# Master.net
KiCad netlist of a schematic drawn in Altium Designer
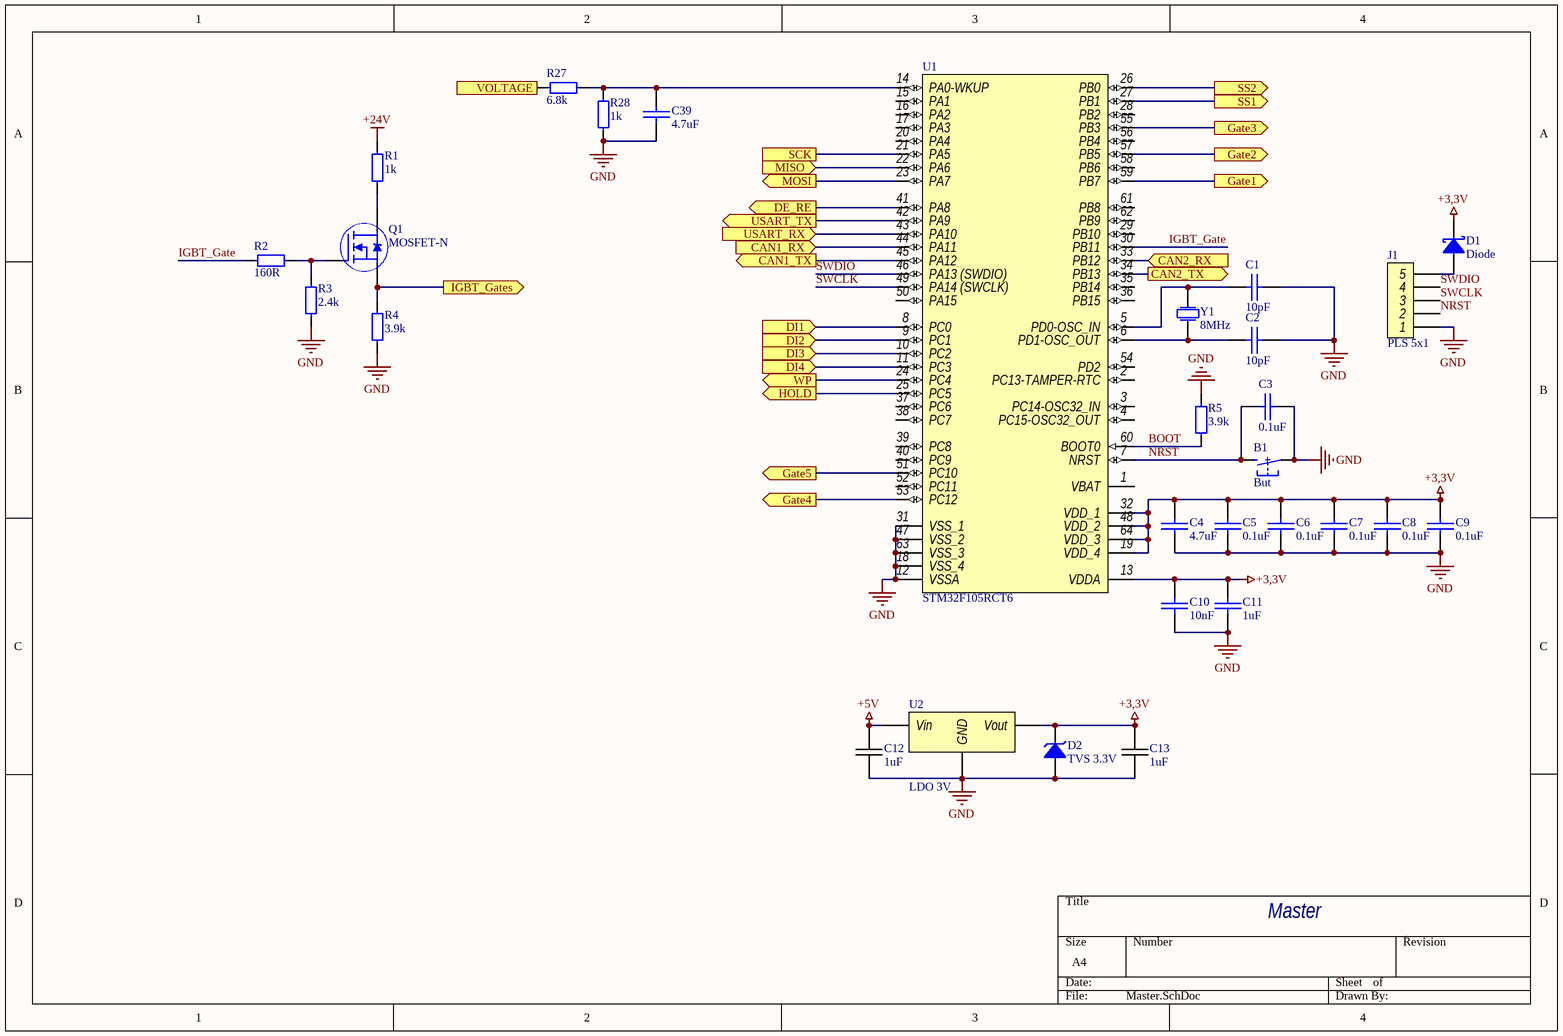
[diagram p0: Master.SchDoc]

(export (version "E")
  (design (tool "Eeschema 10.0.6"))
  (components
    (comp (ref "B1")
      (value "But")
      (footprint "BUTTON 6x3.5")
      (description "Button 2 Conn SMD")
      (fields
        (field (name "PART NUMBER") "L-KLS7-TS3608-5.0-180")
        (field (name "MANUFACTURER") "KLS electronic co ltd")
      )
      (libsource (lib "БУС") (part "Button 2 Conn"))
    )
    (comp (ref "C1")
      (value "10pF")
      (footprint "0603 Capicator")
      (description "10pF NP0 50V 5% 0603")
      (fields
        (field (name "MANUFACTURER") "Murata Manufacturing")
        (field (name "PART NUMBER") "GRM1885C1H100JA01D")
      )
      (libsource (lib "БУС") (part "Cap 10pF (0603)"))
    )
    (comp (ref "C2")
      (value "10pF")
      (footprint "0603 Capicator")
      (description "10pF NP0 50V 5% 0603")
      (fields
        (field (name "MANUFACTURER") "Murata Manufacturing")
        (field (name "PART NUMBER") "GRM1885C1H100JA01D")
      )
      (libsource (lib "БУС") (part "Cap 10pF (0603)"))
    )
    (comp (ref "C3")
      (value "0.1uF")
      (footprint "0603 Capicator")
      (description "0.1uF X7R 16V 10% 0603")
      (fields
        (field (name "MANUFACTURER") "Murata Manufacturing")
        (field (name "PART NUMBER") "GRM188R71C104KA01D")
      )
      (libsource (lib "БУС") (part "Cap 0.1uF (0603)"))
    )
    (comp (ref "C4")
      (value "4.7uF")
      (footprint "0603 Capicator")
      (description "4.7uF X5R 25V 10% 0603")
      (fields
        (field (name "MANUFACTURER") "Murata Manufacturing")
        (field (name "PART NUMBER") "GRM188R61E475KE11D")
      )
      (libsource (lib "БУС") (part "Cap 4.7uF (0603)"))
    )
    (comp (ref "C5")
      (value "0.1uF")
      (footprint "0603 Capicator")
      (description "0.1uF X7R 16V 10% 0603")
      (fields
        (field (name "MANUFACTURER") "Murata Manufacturing")
        (field (name "PART NUMBER") "GRM188R71C104KA01D")
      )
      (libsource (lib "БУС") (part "Cap 0.1uF (0603)"))
    )
    (comp (ref "C6")
      (value "0.1uF")
      (footprint "0603 Capicator")
      (description "0.1uF X7R 16V 10% 0603")
      (fields
        (field (name "MANUFACTURER") "Murata Manufacturing")
        (field (name "PART NUMBER") "GRM188R71C104KA01D")
      )
      (libsource (lib "БУС") (part "Cap 0.1uF (0603)"))
    )
    (comp (ref "C7")
      (value "0.1uF")
      (footprint "0603 Capicator")
      (description "0.1uF X7R 16V 10% 0603")
      (fields
        (field (name "MANUFACTURER") "Murata Manufacturing")
        (field (name "PART NUMBER") "GRM188R71C104KA01D")
      )
      (libsource (lib "БУС") (part "Cap 0.1uF (0603)"))
    )
    (comp (ref "C8")
      (value "0.1uF")
      (footprint "0603 Capicator")
      (description "0.1uF X7R 16V 10% 0603")
      (fields
        (field (name "MANUFACTURER") "Murata Manufacturing")
        (field (name "PART NUMBER") "GRM188R71C104KA01D")
      )
      (libsource (lib "БУС") (part "Cap 0.1uF (0603)"))
    )
    (comp (ref "C9")
      (value "0.1uF")
      (footprint "0603 Capicator")
      (description "0.1uF X7R 16V 10% 0603")
      (fields
        (field (name "MANUFACTURER") "Murata Manufacturing")
        (field (name "PART NUMBER") "GRM188R71C104KA01D")
      )
      (libsource (lib "БУС") (part "Cap 0.1uF (0603)"))
    )
    (comp (ref "C10")
      (value "10nF")
      (footprint "0603 Capicator")
      (description "10nF X7R  100V 10% 0603")
      (fields
        (field (name "MANUFACTURER") "Murata Manufacturing")
        (field (name "PART NUMBER") "GRM188R72A103KA01D")
      )
      (libsource (lib "БУС") (part "Cap 10nF (0603)"))
    )
    (comp (ref "C11")
      (value "1uF")
      (footprint "0603 Capicator")
      (description "1uF X5R 25V 10% 0603")
      (fields
        (field (name "MANUFACTURER") "Murata Manufacturing")
        (field (name "PART NUMBER") "GRM188R61E105KAADD")
      )
      (libsource (lib "БУС") (part "Cap 1uF (0603)"))
    )
    (comp (ref "C12")
      (value "1uF")
      (footprint "0603 Capicator")
      (description "1uF X5R 25V 10% 0603")
      (fields
        (field (name "MANUFACTURER") "Murata Manufacturing")
        (field (name "PART NUMBER") "GRM188R61E105KAADD")
      )
      (libsource (lib "БУС") (part "Cap 1uF (0603)"))
    )
    (comp (ref "C13")
      (value "1uF")
      (footprint "0603 Capicator")
      (description "1uF X5R 25V 10% 0603")
      (fields
        (field (name "MANUFACTURER") "Murata Manufacturing")
        (field (name "PART NUMBER") "GRM188R61E105KAADD")
      )
      (libsource (lib "БУС") (part "Cap 1uF (0603)"))
    )
    (comp (ref "C39")
      (value "4.7uF")
      (footprint "0603 Capicator")
      (description "4.7uF X5R 25V 10% 0603")
      (fields
        (field (name "MANUFACTURER") "Murata Manufacturing")
        (field (name "PART NUMBER") "GRM188R61E475KE11D")
      )
      (libsource (lib "БУНЭ") (part "Cap 4.7uF (0603)"))
    )
    (comp (ref "D1")
      (value "Diode")
      (footprint "sod-123")
      (description "0.5 A, Low Forward Voltage less than 385 mV, 400 mW Power Dissipation Package")
      (fields (field (name "PART NUMBER") "MBR0520L") (field (name "MANUFACTURER") "ON Semiconductor"))
      (libsource (lib "БУС") (part "Diode Schottky (SOD-123)"))
    )
    (comp (ref "D2")
      (value "TVS 3.3V")
      (footprint "DO-216AA")
      (description "High peak pulse power: 200 W (10/1000 μs)")
      (fields (field (name "PART NUMBER") "SM2T3V3A") (field (name "MANUFACTURER") "STMicroelectronics"))
      (libsource (lib "БУС") (part "TVS Diode 3.3V [SM2T]"))
    )
    (comp (ref "J1")
      (value "PLS 5x1")
      (footprint "PLS 5x1")
      (description "Header, 5-Pin")
      (libsource (lib "БУС") (part "Conn 5 (PLS)"))
    )
    (comp (ref "Q1")
      (value "MOSFET-N")
      (footprint "SOT-23")
      (description "VDS 30V,  VGS Max ± 20V, RDS 27-40mΩ,")
      (fields
        (field (name "PART NUMBER") "IRLML0030TRPBF")
        (field (name "MANUFACTURER") "Infineon Technologies")
      )
      (libsource (lib "БУНЭ") (part "MOSFET-N [IRLML]"))
    )
    (comp (ref "R1")
      (value "1k")
      (footprint "0603 Resistor")
      (description "0.1W 0603 1k, 1%")
      (fields (field (name "PART NUMBER") "RC0603FR-071KL") (field (name "MANUFACTURER") "Taiwan"))
      (libsource (lib "БУНЭ") (part "Res 1k (0603)"))
    )
    (comp (ref "R2")
      (value "160R")
      (footprint "0603 Resistor")
      (description "0.1W 0603 160R, 1%")
      (fields (field (name "PART NUMBER") "RC0603FR-07160RL") (field (name "MANUFACTURER") "Taiwan"))
      (libsource (lib "БУС") (part "Res 160R (0603)"))
    )
    (comp (ref "R3")
      (value "2.4k")
      (footprint "0603 Resistor")
      (description "0.1W 0603 2.4k, 1%")
      (fields (field (name "PART NUMBER") "RC0603FR-072K4L") (field (name "MANUFACTURER") "Taiwan"))
      (libsource (lib "БУС") (part "Res 2.4k (0603)"))
    )
    (comp (ref "R4")
      (value "3.9k")
      (footprint "0603 Resistor")
      (description "0.1W 0603 3.9k, 1%")
      (fields (field (name "PART NUMBER") "RC0603FR-073K9L") (field (name "MANUFACTURER") "Taiwan"))
      (libsource (lib "БУНЭ") (part "Res 3.9k (0603)"))
    )
    (comp (ref "R5")
      (value "3.9k")
      (footprint "0603 Resistor")
      (description "0.1W 0603 3.9k, 1%")
      (fields (field (name "PART NUMBER") "RC0603FR-073K9L") (field (name "MANUFACTURER") "Taiwan"))
      (libsource (lib "БУС") (part "Res 3.9k (0603)"))
    )
    (comp (ref "R27")
      (value "6.8k")
      (footprint "0603 Resistor")
      (description "0.1W 0603 6.8k, 1%")
      (fields (field (name "PART NUMBER") "RC0603FR-076K8L") (field (name "MANUFACTURER") "Taiwan"))
      (libsource (lib "БУНЭ") (part "Res 6.8k (0603)"))
    )
    (comp (ref "R28")
      (value "1k")
      (footprint "0603 Resistor")
      (description "0.1W 0603 1k, 1%")
      (fields (field (name "PART NUMBER") "RC0603FR-071KL") (field (name "MANUFACTURER") "Taiwan"))
      (libsource (lib "БУНЭ") (part "Res 1k (0603)"))
    )
    (comp (ref "U1")
      (value "STM32F105RCT6")
      (footprint "LQFP64")
      (description "MCU ARM 256KB FLASH MEM 64-LQFP")
      (fields (field (name "MANUFACTURER") "STMicroelectronics"))
      (libsource (lib "БУС") (part "STM32F105RCT6"))
    )
    (comp (ref "U2")
      (value "LDO 3V")
      (footprint "SOT-23")
      (description "MCP1702 Low Dropout Voltage Regulator. The input operating range is specifiedfrom 2.7V to 13.2V")
      (fields (field (name "PART NUMBER") "MCP1702T-3002E/CB") (field (name "MANUFACTURER") "Microchip"))
      (libsource (lib "БУС") (part "LDO 3,3V [MCP]"))
    )
    (comp (ref "Y1")
      (value "8MHz")
      (footprint "NX5032GA")
      (description "Crystal NX5032GA")
      (fields
        (field (name "MANUFACTURER") "Nihon Dempa Kogio (NDK)")
        (field (name "PART NUMBER") "NX5032GA-8MHz")
      )
      (libsource (lib "БУС") (part "Crystal 8MHz"))
    )
  )
  (nets
    (net (code "1") (name "+3,3V") (class "Default")
      (node (ref "C10") (pin "2") (pinfunction "2_2") (pintype "passive"))
      (node (ref "C11") (pin "2") (pinfunction "2_2") (pintype "passive"))
      (node (ref "C13") (pin "2") (pinfunction "2_2") (pintype "passive"))
      (node (ref "C4") (pin "2") (pinfunction "2_2") (pintype "passive"))
      (node (ref "C5") (pin "2") (pinfunction "2_2") (pintype "passive"))
      (node (ref "C6") (pin "2") (pinfunction "2_2") (pintype "passive"))
      (node (ref "C7") (pin "2") (pinfunction "2_2") (pintype "passive"))
      (node (ref "C8") (pin "2") (pinfunction "2_2") (pintype "passive"))
      (node (ref "C9") (pin "2") (pinfunction "2_2") (pintype "passive"))
      (node (ref "D1") (pin "2") (pinfunction "2_2") (pintype "passive"))
      (node (ref "D2") (pin "2") (pinfunction "2_2") (pintype "passive"))
      (node (ref "U1") (pin "13") (pinfunction "VDDA_13") (pintype "power_in"))
      (node (ref "U1") (pin "19") (pinfunction "VDD_4_19") (pintype "power_in"))
      (node (ref "U1") (pin "32") (pinfunction "VDD_1_32") (pintype "power_in"))
      (node (ref "U1") (pin "48") (pinfunction "VDD_2_48") (pintype "power_in"))
      (node (ref "U1") (pin "64") (pinfunction "VDD_3_64") (pintype "power_in"))
      (node (ref "U2") (pin "2") (pinfunction "Vout_2") (pintype "power_in"))
    )
    (net (code "2") (name "+5V") (class "Default")
      (node (ref "C12") (pin "2") (pinfunction "2_2") (pintype "passive"))
      (node (ref "U2") (pin "3") (pinfunction "Vin_3") (pintype "power_in"))
    )
    (net (code "3") (name "+24V") (class "Default")
      (node (ref "R1") (pin "2") (pinfunction "2_2") (pintype "passive"))
    )
    (net (code "4") (name "/BOOT") (class "Default")
      (node (ref "R5") (pin "1") (pinfunction "1_1") (pintype "passive"))
      (node (ref "U1") (pin "60") (pinfunction "BOOT0_60") (pintype "input"))
    )
    (net (code "5") (name "/CAN1_RX") (class "Default")
      (node (ref "U1") (pin "44") (pinfunction "PA11_44") (pintype "bidirectional"))
    )
    (net (code "6") (name "/CAN1_TX") (class "Default")
      (node (ref "U1") (pin "45") (pinfunction "PA12_45") (pintype "bidirectional"))
    )
    (net (code "7") (name "/CAN2_RX") (class "Default")
      (node (ref "U1") (pin "33") (pinfunction "PB12_33") (pintype "bidirectional"))
    )
    (net (code "8") (name "/CAN2_TX") (class "Default")
      (node (ref "U1") (pin "34") (pinfunction "PB13_34") (pintype "bidirectional"))
    )
    (net (code "9") (name "/DE_RE") (class "Default")
      (node (ref "U1") (pin "41") (pinfunction "PA8_41") (pintype "bidirectional"))
    )
    (net (code "10") (name "/DI1") (class "Default")
      (node (ref "U1") (pin "8") (pinfunction "PC0_8") (pintype "bidirectional"))
    )
    (net (code "11") (name "/DI2") (class "Default")
      (node (ref "U1") (pin "9") (pinfunction "PC1_9") (pintype "bidirectional"))
    )
    (net (code "12") (name "/DI3") (class "Default")
      (node (ref "U1") (pin "10") (pinfunction "PC2_10") (pintype "bidirectional"))
    )
    (net (code "13") (name "/DI4") (class "Default")
      (node (ref "U1") (pin "11") (pinfunction "PC3_11") (pintype "bidirectional"))
    )
    (net (code "14") (name "/Gate1") (class "Default")
      (node (ref "U1") (pin "59") (pinfunction "PB7_59") (pintype "bidirectional"))
    )
    (net (code "15") (name "/Gate2") (class "Default")
      (node (ref "U1") (pin "57") (pinfunction "PB5_57") (pintype "bidirectional"))
    )
    (net (code "16") (name "/Gate3") (class "Default")
      (node (ref "U1") (pin "55") (pinfunction "PB3_55") (pintype "bidirectional"))
    )
    (net (code "17") (name "/Gate4") (class "Default")
      (node (ref "U1") (pin "53") (pinfunction "PC12_53") (pintype "bidirectional"))
    )
    (net (code "18") (name "/Gate5") (class "Default")
      (node (ref "U1") (pin "51") (pinfunction "PC10_51") (pintype "bidirectional"))
    )
    (net (code "19") (name "/HOLD") (class "Default")
      (node (ref "U1") (pin "25") (pinfunction "PC5_25") (pintype "bidirectional"))
    )
    (net (code "20") (name "/IGBT_Gate") (class "Default")
      (node (ref "R2") (pin "1") (pinfunction "1_1") (pintype "passive"))
      (node (ref "U1") (pin "30") (pinfunction "PB11_30") (pintype "bidirectional"))
    )
    (net (code "21") (name "/IGBT_Gates") (class "Default")
      (node (ref "Q1") (pin "2") (pinfunction "Source_2") (pintype "passive"))
      (node (ref "R4") (pin "2") (pinfunction "2_2") (pintype "passive"))
    )
    (net (code "22") (name "/MISO") (class "Default")
      (node (ref "U1") (pin "22") (pinfunction "PA6_22") (pintype "bidirectional"))
    )
    (net (code "23") (name "/MOSI") (class "Default")
      (node (ref "U1") (pin "23") (pinfunction "PA7_23") (pintype "bidirectional"))
    )
    (net (code "24") (name "/NRST") (class "Default")
      (node (ref "B1") (pin "2") (pinfunction "2_2") (pintype "passive"))
      (node (ref "C3") (pin "1") (pinfunction "1_1") (pintype "passive"))
      (node (ref "J1") (pin "2") (pinfunction "2_2") (pintype "passive"))
      (node (ref "U1") (pin "7") (pinfunction "NRST_7") (pintype "bidirectional"))
    )
    (net (code "25") (name "/SCK") (class "Default")
      (node (ref "U1") (pin "21") (pinfunction "PA5_21") (pintype "bidirectional"))
    )
    (net (code "26") (name "/SS1") (class "Default")
      (node (ref "U1") (pin "27") (pinfunction "PB1_27") (pintype "bidirectional"))
    )
    (net (code "27") (name "/SS2") (class "Default")
      (node (ref "U1") (pin "26") (pinfunction "PB0_26") (pintype "bidirectional"))
    )
    (net (code "28") (name "/SWCLK") (class "Default")
      (node (ref "J1") (pin "3") (pinfunction "3_3") (pintype "passive"))
      (node (ref "U1") (pin "49") (pinfunction "PA14_(SWCLK)_49") (pintype "bidirectional"))
    )
    (net (code "29") (name "/SWDIO") (class "Default")
      (node (ref "J1") (pin "4") (pinfunction "4_4") (pintype "passive"))
      (node (ref "U1") (pin "46") (pinfunction "PA13_(SWDIO)_46") (pintype "bidirectional"))
    )
    (net (code "30") (name "/USART_RX") (class "Default")
      (node (ref "U1") (pin "43") (pinfunction "PA10_43") (pintype "bidirectional"))
    )
    (net (code "31") (name "/USART_TX") (class "Default")
      (node (ref "U1") (pin "42") (pinfunction "PA9_42") (pintype "bidirectional"))
    )
    (net (code "32") (name "/VOLTAGE") (class "Default")
      (node (ref "R27") (pin "2") (pinfunction "2_2") (pintype "passive"))
    )
    (net (code "33") (name "/WP") (class "Default")
      (node (ref "U1") (pin "24") (pinfunction "PC4_24") (pintype "bidirectional"))
    )
    (net (code "34") (name "GND") (class "Default")
      (node (ref "B1") (pin "1") (pinfunction "1_1") (pintype "passive"))
      (node (ref "C1") (pin "2") (pinfunction "2_2") (pintype "passive"))
      (node (ref "C10") (pin "1") (pinfunction "1_1") (pintype "passive"))
      (node (ref "C11") (pin "1") (pinfunction "1_1") (pintype "passive"))
      (node (ref "C12") (pin "1") (pinfunction "1_1") (pintype "passive"))
      (node (ref "C13") (pin "1") (pinfunction "1_1") (pintype "passive"))
      (node (ref "C2") (pin "2") (pinfunction "2_2") (pintype "passive"))
      (node (ref "C3") (pin "2") (pinfunction "2_2") (pintype "passive"))
      (node (ref "C39") (pin "1") (pinfunction "1_1") (pintype "passive"))
      (node (ref "C4") (pin "1") (pinfunction "1_1") (pintype "passive"))
      (node (ref "C5") (pin "1") (pinfunction "1_1") (pintype "passive"))
      (node (ref "C6") (pin "1") (pinfunction "1_1") (pintype "passive"))
      (node (ref "C7") (pin "1") (pinfunction "1_1") (pintype "passive"))
      (node (ref "C8") (pin "1") (pinfunction "1_1") (pintype "passive"))
      (node (ref "C9") (pin "1") (pinfunction "1_1") (pintype "passive"))
      (node (ref "D2") (pin "1") (pinfunction "1_1") (pintype "passive"))
      (node (ref "J1") (pin "1") (pinfunction "1_1") (pintype "passive"))
      (node (ref "R28") (pin "1") (pinfunction "1_1") (pintype "passive"))
      (node (ref "R3") (pin "1") (pinfunction "1_1") (pintype "passive"))
      (node (ref "R4") (pin "1") (pinfunction "1_1") (pintype "passive"))
      (node (ref "R5") (pin "2") (pinfunction "2_2") (pintype "passive"))
      (node (ref "U1") (pin "12") (pinfunction "VSSA_12") (pintype "power_in"))
      (node (ref "U1") (pin "18") (pinfunction "VSS_4_18") (pintype "power_in"))
      (node (ref "U1") (pin "31") (pinfunction "VSS_1_31") (pintype "power_in"))
      (node (ref "U1") (pin "47") (pinfunction "VSS_2_47") (pintype "power_in"))
      (node (ref "U1") (pin "63") (pinfunction "VSS_3_63") (pintype "power_in"))
      (node (ref "U2") (pin "1") (pinfunction "GND_1") (pintype "power_in"))
    )
    (net (code "35") (name "Net-(D1-Pad1)") (class "Default")
      (node (ref "D1") (pin "1") (pinfunction "1_1") (pintype "passive"))
      (node (ref "J1") (pin "5") (pinfunction "5_5") (pintype "passive"))
    )
    (net (code "36") (name "Net-(Q1-Drain)") (class "Default")
      (node (ref "Q1") (pin "3") (pinfunction "Drain_3") (pintype "passive"))
      (node (ref "R1") (pin "1") (pinfunction "1_1") (pintype "passive"))
    )
    (net (code "37") (name "Net-(Q1-Gate)") (class "Default")
      (node (ref "Q1") (pin "1") (pinfunction "Gate_1") (pintype "passive"))
      (node (ref "R2") (pin "2") (pinfunction "2_2") (pintype "passive"))
      (node (ref "R3") (pin "2") (pinfunction "2_2") (pintype "passive"))
    )
    (net (code "38") (name "Net-(U1-PA0-WKUP)") (class "Default")
      (node (ref "C39") (pin "2") (pinfunction "2_2") (pintype "passive"))
      (node (ref "R27") (pin "1") (pinfunction "1_1") (pintype "passive"))
      (node (ref "R28") (pin "2") (pinfunction "2_2") (pintype "passive"))
      (node (ref "U1") (pin "14") (pinfunction "PA0-WKUP_14") (pintype "bidirectional"))
    )
    (net (code "39") (name "Net-(U1-PD0-OSC_IN)") (class "Default")
      (node (ref "C1") (pin "1") (pinfunction "1_1") (pintype "passive"))
      (node (ref "U1") (pin "5") (pinfunction "PD0-OSC_IN_5") (pintype "bidirectional"))
      (node (ref "Y1") (pin "2") (pinfunction "2_2") (pintype "passive"))
    )
    (net (code "40") (name "Net-(U1-PD1-OSC_OUT)") (class "Default")
      (node (ref "C2") (pin "1") (pinfunction "1_1") (pintype "passive"))
      (node (ref "U1") (pin "6") (pinfunction "PD1-OSC_OUT_6") (pintype "bidirectional"))
      (node (ref "Y1") (pin "1") (pinfunction "1_1") (pintype "passive"))
    )
    (net (code "41") (name "unconnected-(U1-PA1-Pad15)") (class "Default")
      (node (ref "U1") (pin "15") (pinfunction "PA1_15") (pintype "bidirectional"))
    )
    (net (code "42") (name "unconnected-(U1-PA2-Pad16)") (class "Default")
      (node (ref "U1") (pin "16") (pinfunction "PA2_16") (pintype "bidirectional"))
    )
    (net (code "43") (name "unconnected-(U1-PA3-Pad17)") (class "Default")
      (node (ref "U1") (pin "17") (pinfunction "PA3_17") (pintype "bidirectional"))
    )
    (net (code "44") (name "unconnected-(U1-PA4-Pad20)") (class "Default")
      (node (ref "U1") (pin "20") (pinfunction "PA4_20") (pintype "bidirectional"))
    )
    (net (code "45") (name "unconnected-(U1-PA15-Pad50)") (class "Default")
      (node (ref "U1") (pin "50") (pinfunction "PA15_50") (pintype "bidirectional"))
    )
    (net (code "46") (name "unconnected-(U1-PB2-Pad28)") (class "Default")
      (node (ref "U1") (pin "28") (pinfunction "PB2_28") (pintype "bidirectional"))
    )
    (net (code "47") (name "unconnected-(U1-PB4-Pad56)") (class "Default")
      (node (ref "U1") (pin "56") (pinfunction "PB4_56") (pintype "bidirectional"))
    )
    (net (code "48") (name "unconnected-(U1-PB6-Pad58)") (class "Default")
      (node (ref "U1") (pin "58") (pinfunction "PB6_58") (pintype "bidirectional"))
    )
    (net (code "49") (name "unconnected-(U1-PB8-Pad61)") (class "Default")
      (node (ref "U1") (pin "61") (pinfunction "PB8_61") (pintype "bidirectional"))
    )
    (net (code "50") (name "unconnected-(U1-PB9-Pad62)") (class "Default")
      (node (ref "U1") (pin "62") (pinfunction "PB9_62") (pintype "bidirectional"))
    )
    (net (code "51") (name "unconnected-(U1-PB10-Pad29)") (class "Default")
      (node (ref "U1") (pin "29") (pinfunction "PB10_29") (pintype "bidirectional"))
    )
    (net (code "52") (name "unconnected-(U1-PB14-Pad35)") (class "Default")
      (node (ref "U1") (pin "35") (pinfunction "PB14_35") (pintype "bidirectional"))
    )
    (net (code "53") (name "unconnected-(U1-PB15-Pad36)") (class "Default")
      (node (ref "U1") (pin "36") (pinfunction "PB15_36") (pintype "bidirectional"))
    )
    (net (code "54") (name "unconnected-(U1-PC6-Pad37)") (class "Default")
      (node (ref "U1") (pin "37") (pinfunction "PC6_37") (pintype "bidirectional"))
    )
    (net (code "55") (name "unconnected-(U1-PC7-Pad38)") (class "Default")
      (node (ref "U1") (pin "38") (pinfunction "PC7_38") (pintype "bidirectional"))
    )
    (net (code "56") (name "unconnected-(U1-PC8-Pad39)") (class "Default")
      (node (ref "U1") (pin "39") (pinfunction "PC8_39") (pintype "bidirectional"))
    )
    (net (code "57") (name "unconnected-(U1-PC9-Pad40)") (class "Default")
      (node (ref "U1") (pin "40") (pinfunction "PC9_40") (pintype "bidirectional"))
    )
    (net (code "58") (name "unconnected-(U1-PC11-Pad52)") (class "Default")
      (node (ref "U1") (pin "52") (pinfunction "PC11_52") (pintype "bidirectional"))
    )
    (net (code "59") (name "unconnected-(U1-PC13-TAMPER-RTC-Pad2)") (class "Default")
      (node (ref "U1") (pin "2") (pinfunction "PC13-TAMPER-RTC_2") (pintype "bidirectional"))
    )
    (net (code "60") (name "unconnected-(U1-PC14-OSC32_IN-Pad3)") (class "Default")
      (node (ref "U1") (pin "3") (pinfunction "PC14-OSC32_IN_3") (pintype "bidirectional"))
    )
    (net (code "61") (name "unconnected-(U1-PC15-OSC32_OUT-Pad4)") (class "Default")
      (node (ref "U1") (pin "4") (pinfunction "PC15-OSC32_OUT_4") (pintype "bidirectional"))
    )
    (net (code "62") (name "unconnected-(U1-PD2-Pad54)") (class "Default")
      (node (ref "U1") (pin "54") (pinfunction "PD2_54") (pintype "bidirectional"))
    )
    (net (code "63") (name "unconnected-(U1-VBAT-Pad1)") (class "Default")
      (node (ref "U1") (pin "1") (pinfunction "VBAT_1") (pintype "power_in"))
    )
  )
)
